# pcuTC.net
KiCad netlist of a schematic drawn in Altium Designer
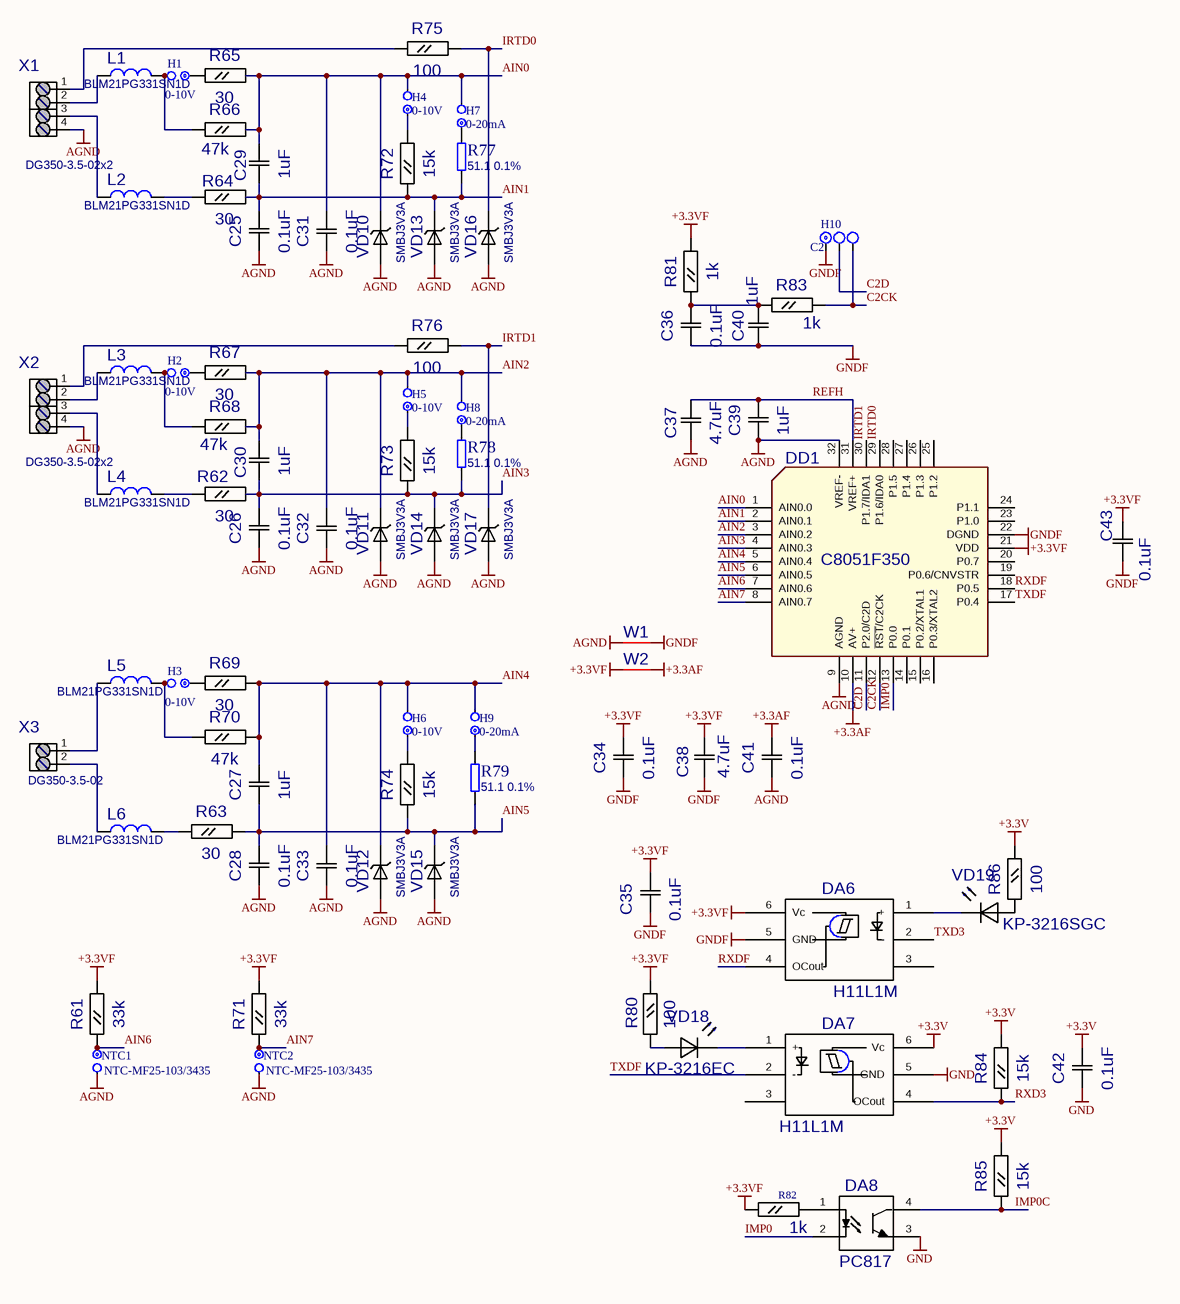
[diagram p0: pcuTC.SchDoc]

(export (version "E")
  (design (tool "Eeschema 10.0.6"))
  (components
    (comp (ref "C25")
      (value "0.1uF")
      (footprint "C0805")
      (description "C0805")
      (libsource (lib "FurmansLib") (part "C0805"))
    )
    (comp (ref "C26")
      (value "0.1uF")
      (footprint "C0805")
      (description "C0805")
      (libsource (lib "FurmansLib") (part "C0805"))
    )
    (comp (ref "C27")
      (value "1uF")
      (footprint "C0805")
      (description "C0805")
      (libsource (lib "FurmansLib") (part "C0805"))
    )
    (comp (ref "C28")
      (value "0.1uF")
      (footprint "C0805")
      (description "C0805")
      (libsource (lib "FurmansLib") (part "C0805"))
    )
    (comp (ref "C29")
      (value "1uF")
      (footprint "C0805")
      (description "C0805")
      (libsource (lib "FurmansLib") (part "C0805"))
    )
    (comp (ref "C30")
      (value "1uF")
      (footprint "C0805")
      (description "C0805")
      (libsource (lib "FurmansLib") (part "C0805"))
    )
    (comp (ref "C31")
      (value "0.1uF")
      (footprint "C0805")
      (description "C0805")
      (libsource (lib "FurmansLib") (part "C0805"))
    )
    (comp (ref "C32")
      (value "0.1uF")
      (footprint "C0805")
      (description "C0805")
      (libsource (lib "FurmansLib") (part "C0805"))
    )
    (comp (ref "C33")
      (value "0.1uF")
      (footprint "C0805")
      (description "C0805")
      (libsource (lib "FurmansLib") (part "C0805"))
    )
    (comp (ref "C34")
      (value "0.1uF")
      (footprint "C0805")
      (description "C0805")
      (libsource (lib "FurmansLib") (part "C0805"))
    )
    (comp (ref "C35")
      (value "0.1uF")
      (footprint "C0805")
      (description "C0805")
      (libsource (lib "FurmansLib") (part "C0805"))
    )
    (comp (ref "C36")
      (value "0.1uF")
      (footprint "C0805")
      (description "C0805")
      (libsource (lib "FurmansLib") (part "C0805"))
    )
    (comp (ref "C37")
      (value "4.7uF")
      (footprint "C0805")
      (description "C0805")
      (libsource (lib "FurmansLib") (part "C0805"))
    )
    (comp (ref "C38")
      (value "4.7uF")
      (footprint "C0805")
      (description "C0805")
      (libsource (lib "FurmansLib") (part "C0805"))
    )
    (comp (ref "C39")
      (value "1uF")
      (footprint "C0805")
      (description "C0805")
      (libsource (lib "FurmansLib") (part "C0805"))
    )
    (comp (ref "C40")
      (value "1uF")
      (footprint "C0805")
      (description "C0805")
      (libsource (lib "FurmansLib") (part "C0805"))
    )
    (comp (ref "C41")
      (value "0.1uF")
      (footprint "C0805")
      (description "C0805")
      (libsource (lib "FurmansLib") (part "C0805"))
    )
    (comp (ref "C42")
      (value "0.1uF")
      (footprint "C0805")
      (description "C0805")
      (libsource (lib "FurmansLib") (part "C0805"))
    )
    (comp (ref "C43")
      (value "0.1uF")
      (footprint "C0805")
      (description "C0805")
      (libsource (lib "FurmansLib") (part "C0805"))
    )
    (comp (ref "DA6") (value "H11L1M") (footprint "DIP6_SURFACE") (libsource (lib "") (part "H11L1M_1")))
    (comp (ref "DA7") (value "H11L1M") (footprint "DIP6_SURFACE") (libsource (lib "*") (part "H11L1M")))
    (comp (ref "DA8")
      (value "PC817")
      (footprint "DIL4SMD")
      (description "optocuple")
      (libsource (lib "FurmansLib") (part "PC817"))
    )
    (comp (ref "DD1")
      (value "C8051F350")
      (footprint "LQFP-32_N")
      (libsource (lib "FurmansLib") (part "C8051F350"))
    )
    (comp (ref "H1")
      (value "~")
      (footprint "J1x2")
      (fields (field (name "ALTIUM_UNNAMED_2") "0-10V"))
      (libsource (lib "FurmansLib") (part "H-1x2"))
    )
    (comp (ref "H2")
      (value "~")
      (footprint "J1x2")
      (fields (field (name "ALTIUM_UNNAMED_2") "0-10V"))
      (libsource (lib "FurmansLib") (part "H-1x2"))
    )
    (comp (ref "H3")
      (value "~")
      (footprint "J1x2")
      (fields (field (name "ALTIUM_UNNAMED_2") "0-10V"))
      (libsource (lib "FurmansLib") (part "H-1x2"))
    )
    (comp (ref "H4")
      (value "~")
      (footprint "J1x2")
      (fields (field (name "ALTIUM_UNNAMED_2") "0-10V"))
      (libsource (lib "FurmansLib") (part "H-1x2"))
    )
    (comp (ref "H5")
      (value "~")
      (footprint "J1x2")
      (fields (field (name "ALTIUM_UNNAMED_2") "0-10V"))
      (libsource (lib "FurmansLib") (part "H-1x2"))
    )
    (comp (ref "H6")
      (value "~")
      (footprint "J1x2")
      (fields (field (name "ALTIUM_UNNAMED_2") "0-10V"))
      (libsource (lib "FurmansLib") (part "H-1x2"))
    )
    (comp (ref "H7")
      (value "~")
      (footprint "J1x2")
      (fields (field (name "ALTIUM_UNNAMED_2") "0-20mA"))
      (libsource (lib "FurmansLib") (part "H-1x2"))
    )
    (comp (ref "H8")
      (value "~")
      (footprint "J1x2")
      (fields (field (name "ALTIUM_UNNAMED_2") "0-20mA"))
      (libsource (lib "FurmansLib") (part "H-1x2"))
    )
    (comp (ref "H9")
      (value "~")
      (footprint "J1x2")
      (fields (field (name "ALTIUM_UNNAMED_2") "0-20mA"))
      (libsource (lib "FurmansLib") (part "H-1x2"))
    )
    (comp (ref "H10") (value "C2") (footprint "J1x3") (libsource (lib "FurmansLib") (part "H-1x3")))
    (comp (ref "L1")
      (value "BLM21PG331SN1D")
      (footprint "R0805")
      (description "Ferrite beads")
      (libsource (lib "FurmansLib") (part "BLM21PG331SN1D"))
    )
    (comp (ref "L2")
      (value "BLM21PG331SN1D")
      (footprint "R0805")
      (description "Ferrite beads")
      (libsource (lib "FurmansLib") (part "BLM21PG331SN1D"))
    )
    (comp (ref "L3")
      (value "BLM21PG331SN1D")
      (footprint "R0805")
      (description "Ferrite beads")
      (libsource (lib "FurmansLib") (part "BLM21PG331SN1D"))
    )
    (comp (ref "L4")
      (value "BLM21PG331SN1D")
      (footprint "R0805")
      (description "Ferrite beads")
      (libsource (lib "FurmansLib") (part "BLM21PG331SN1D"))
    )
    (comp (ref "L5")
      (value "BLM21PG331SN1D")
      (footprint "R0805")
      (description "Ferrite beads")
      (libsource (lib "FurmansLib") (part "BLM21PG331SN1D"))
    )
    (comp (ref "L6")
      (value "BLM21PG331SN1D")
      (footprint "R0805")
      (description "Ferrite beads")
      (libsource (lib "FurmansLib") (part "BLM21PG331SN1D"))
    )
    (comp (ref "NTC1")
      (value "~")
      (footprint "J1x2")
      (fields (field (name "ALTIUM_UNNAMED_1") "NTC-MF25-103/3435"))
      (libsource (lib "FurmansLib") (part "H-1x2"))
    )
    (comp (ref "NTC2")
      (value "~")
      (footprint "J1x2")
      (fields (field (name "ALTIUM_UNNAMED_1") "NTC-MF25-103/3435"))
      (libsource (lib "FurmansLib") (part "H-1x2"))
    )
    (comp (ref "R61")
      (value "33k")
      (footprint "R0805")
      (description "R0805")
      (libsource (lib "FurmansLib") (part "R0805"))
    )
    (comp (ref "R62")
      (value "30")
      (footprint "R0805")
      (description "R0805")
      (libsource (lib "FurmansLib") (part "R0805"))
    )
    (comp (ref "R63")
      (value "30")
      (footprint "R0805")
      (description "R0805")
      (libsource (lib "FurmansLib") (part "R0805"))
    )
    (comp (ref "R64")
      (value "30")
      (footprint "R0805")
      (description "R0805")
      (libsource (lib "FurmansLib") (part "R0805"))
    )
    (comp (ref "R65")
      (value "30")
      (footprint "R0805")
      (description "R0805")
      (libsource (lib "FurmansLib") (part "R0805"))
    )
    (comp (ref "R66")
      (value "47k")
      (footprint "R0805")
      (description "R0805")
      (libsource (lib "FurmansLib") (part "R0805"))
    )
    (comp (ref "R67")
      (value "30")
      (footprint "R0805")
      (description "R0805")
      (libsource (lib "FurmansLib") (part "R0805"))
    )
    (comp (ref "R68")
      (value "47k")
      (footprint "R0805")
      (description "R0805")
      (libsource (lib "FurmansLib") (part "R0805"))
    )
    (comp (ref "R69")
      (value "30")
      (footprint "R0805")
      (description "R0805")
      (libsource (lib "FurmansLib") (part "R0805"))
    )
    (comp (ref "R70")
      (value "47k")
      (footprint "R0805")
      (description "R0805")
      (libsource (lib "FurmansLib") (part "R0805"))
    )
    (comp (ref "R71")
      (value "33k")
      (footprint "R0805")
      (description "R0805")
      (libsource (lib "FurmansLib") (part "R0805"))
    )
    (comp (ref "R72")
      (value "15k")
      (footprint "R0805")
      (description "R0805")
      (libsource (lib "FurmansLib") (part "R0805"))
    )
    (comp (ref "R73")
      (value "15k")
      (footprint "R0805")
      (description "R0805")
      (libsource (lib "FurmansLib") (part "R0805"))
    )
    (comp (ref "R74")
      (value "15k")
      (footprint "R0805")
      (description "R0805")
      (libsource (lib "FurmansLib") (part "R0805"))
    )
    (comp (ref "R75")
      (value "100")
      (footprint "R0805")
      (description "R0805")
      (libsource (lib "FurmansLib") (part "R0805"))
    )
    (comp (ref "R76")
      (value "100")
      (footprint "R0805")
      (description "R0805")
      (libsource (lib "FurmansLib") (part "R0805"))
    )
    (comp (ref "R77")
      (value "51.1 0.1%")
      (footprint "R0.25-300")
      (description "0.25W 5% 250V")
      (libsource (lib "Rez-Axial Pot") (part "R-0.25W"))
    )
    (comp (ref "R78")
      (value "51.1 0.1%")
      (footprint "R0.25-300")
      (description "0.25W 5% 250V")
      (libsource (lib "Rez-Axial Pot") (part "R-0.25W"))
    )
    (comp (ref "R79")
      (value "51.1 0.1%")
      (footprint "R0.25-300")
      (description "0.25W 5% 250V")
      (libsource (lib "Rez-Axial Pot") (part "R-0.25W"))
    )
    (comp (ref "R80")
      (value "100")
      (footprint "R0805")
      (description "R0805")
      (libsource (lib "*") (part "R0805"))
    )
    (comp (ref "R81")
      (value "1k")
      (footprint "R0805")
      (description "R0805")
      (libsource (lib "FurmansLib") (part "R0805"))
    )
    (comp (ref "R82")
      (value "1k")
      (footprint "R0805")
      (description "R0805")
      (libsource (lib "FurmansLib") (part "R0805"))
    )
    (comp (ref "R83")
      (value "1k")
      (footprint "R0805")
      (description "R0805")
      (libsource (lib "FurmansLib") (part "R0805"))
    )
    (comp (ref "R84")
      (value "15k")
      (footprint "R0805")
      (description "R0805")
      (libsource (lib "FurmansLib") (part "R0805"))
    )
    (comp (ref "R85")
      (value "15k")
      (footprint "R0805")
      (description "R0805")
      (libsource (lib "FurmansLib") (part "R0805"))
    )
    (comp (ref "R86")
      (value "100")
      (footprint "R0805")
      (description "R0805")
      (libsource (lib "*") (part "R0805"))
    )
    (comp (ref "VD10")
      (value "SMBJ3V3A")
      (footprint "DO-214AA(SMB)")
      (description "10BQ100")
      (libsource (lib "FurmansLib") (part "10BQ100"))
    )
    (comp (ref "VD11")
      (value "SMBJ3V3A")
      (footprint "DO-214AA(SMB)")
      (description "10BQ100")
      (libsource (lib "FurmansLib") (part "10BQ100"))
    )
    (comp (ref "VD12")
      (value "SMBJ3V3A")
      (footprint "DO-214AA(SMB)")
      (description "10BQ100")
      (libsource (lib "FurmansLib") (part "10BQ100"))
    )
    (comp (ref "VD13")
      (value "SMBJ3V3A")
      (footprint "DO-214AA(SMB)")
      (description "10BQ100")
      (libsource (lib "FurmansLib") (part "10BQ100"))
    )
    (comp (ref "VD14")
      (value "SMBJ3V3A")
      (footprint "DO-214AA(SMB)")
      (description "10BQ100")
      (libsource (lib "FurmansLib") (part "10BQ100"))
    )
    (comp (ref "VD15")
      (value "SMBJ3V3A")
      (footprint "DO-214AA(SMB)")
      (description "10BQ100")
      (libsource (lib "FurmansLib") (part "10BQ100"))
    )
    (comp (ref "VD16")
      (value "SMBJ3V3A")
      (footprint "DO-214AA(SMB)")
      (description "10BQ100")
      (libsource (lib "FurmansLib") (part "10BQ100"))
    )
    (comp (ref "VD17")
      (value "SMBJ3V3A")
      (footprint "DO-214AA(SMB)")
      (description "10BQ100")
      (libsource (lib "FurmansLib") (part "10BQ100"))
    )
    (comp (ref "VD18") (value "KP-3216EC") (footprint "KP-3216") (libsource (lib "*") (part "KP-3216EC")))
    (comp (ref "VD19") (value "KP-3216SGC") (footprint "KP-3216") (libsource (lib "*") (part "KP-3216SGC")))
    (comp (ref "W1")
      (value "Net connector")
      (footprint "FurmansLib:Net connector0.5mm")
      (description "NET CONNECTOR")
      (libsource (lib "Furmans") (part "Net connector"))
    )
    (comp (ref "W2")
      (value "Net connector")
      (footprint "FurmansLib:Net connector0.5mm")
      (description "NET CONNECTOR")
      (libsource (lib "Furmans") (part "Net connector"))
    )
    (comp (ref "X1")
      (value "DG350-3.5-02x2")
      (footprint "DG350-3.5-04 SLIM - duplicate")
      (libsource (lib "FurmansLib") (part "DG350-3.5-04"))
    )
    (comp (ref "X2")
      (value "DG350-3.5-02x2")
      (footprint "DG350-3.5-04 SLIM - duplicate")
      (libsource (lib "FurmansLib") (part "DG350-3.5-04"))
    )
    (comp (ref "X3")
      (value "DG350-3.5-02")
      (footprint "DG350-3.5-02 SLIM")
      (libsource (lib "FurmansLib") (part "DG350-3.5-02"))
    )
  )
  (nets
    (net (code "1") (name "+3.3AF") (class "Default")
      (node (ref "C41") (pin "2") (pintype "passive"))
      (node (ref "DD1") (pin "10") (pinfunction "AV+_10") (pintype "passive"))
      (node (ref "W2") (pin "1") (pintype "passive"))
    )
    (net (code "2") (name "+3.3V") (class "Default")
      (node (ref "C42") (pin "2") (pintype "passive"))
      (node (ref "DA7") (pin "6") (pinfunction "Vc_6") (pintype "passive"))
      (node (ref "R84") (pin "1") (pintype "passive"))
      (node (ref "R85") (pin "1") (pintype "passive"))
      (node (ref "R86") (pin "2") (pintype "passive"))
    )
    (net (code "3") (name "+3.3VF") (class "Default")
      (node (ref "C34") (pin "2") (pintype "passive"))
      (node (ref "C35") (pin "1") (pintype "passive"))
      (node (ref "C38") (pin "2") (pintype "passive"))
      (node (ref "C43") (pin "2") (pintype "passive"))
      (node (ref "DA6") (pin "6") (pinfunction "Vc_6") (pintype "passive"))
      (node (ref "DD1") (pin "21") (pinfunction "VDD_21") (pintype "passive"))
      (node (ref "R61") (pin "1") (pintype "passive"))
      (node (ref "R71") (pin "1") (pintype "passive"))
      (node (ref "R80") (pin "2") (pintype "passive"))
      (node (ref "R81") (pin "1") (pintype "passive"))
      (node (ref "R82") (pin "2") (pintype "passive"))
      (node (ref "W2") (pin "2") (pintype "passive"))
    )
    (net (code "4") (name "/AIN0") (class "Default")
      (node (ref "C29") (pin "2") (pintype "passive"))
      (node (ref "C31") (pin "1") (pintype "passive"))
      (node (ref "DD1") (pin "1") (pinfunction "AIN0.0_1") (pintype "passive"))
      (node (ref "H4") (pin "2") (pinfunction "2_2") (pintype "passive"))
      (node (ref "H7") (pin "2") (pinfunction "2_2") (pintype "passive"))
      (node (ref "R65") (pin "1") (pintype "passive"))
      (node (ref "R66") (pin "1") (pintype "passive"))
      (node (ref "VD10") (pin "1") (pintype "passive"))
    )
    (net (code "5") (name "/AIN1") (class "Default")
      (node (ref "C25") (pin "2") (pintype "passive"))
      (node (ref "C29") (pin "1") (pintype "passive"))
      (node (ref "DD1") (pin "2") (pinfunction "AIN0.1_2") (pintype "passive"))
      (node (ref "R64") (pin "1") (pintype "passive"))
      (node (ref "R72") (pin "2") (pintype "passive"))
      (node (ref "R77") (pin "1") (pinfunction "1_1") (pintype "passive"))
      (node (ref "VD13") (pin "1") (pintype "passive"))
    )
    (net (code "6") (name "/AIN2") (class "Default")
      (node (ref "C30") (pin "2") (pintype "passive"))
      (node (ref "C32") (pin "1") (pintype "passive"))
      (node (ref "DD1") (pin "3") (pinfunction "AIN0.2_3") (pintype "passive"))
      (node (ref "H5") (pin "2") (pinfunction "2_2") (pintype "passive"))
      (node (ref "H8") (pin "2") (pinfunction "2_2") (pintype "passive"))
      (node (ref "R67") (pin "1") (pintype "passive"))
      (node (ref "R68") (pin "1") (pintype "passive"))
      (node (ref "VD11") (pin "1") (pintype "passive"))
    )
    (net (code "7") (name "/AIN3") (class "Default")
      (node (ref "C26") (pin "2") (pintype "passive"))
      (node (ref "C30") (pin "1") (pintype "passive"))
      (node (ref "DD1") (pin "4") (pinfunction "AIN0.3_4") (pintype "passive"))
      (node (ref "R62") (pin "1") (pintype "passive"))
      (node (ref "R73") (pin "2") (pintype "passive"))
      (node (ref "R78") (pin "1") (pinfunction "1_1") (pintype "passive"))
      (node (ref "VD14") (pin "1") (pintype "passive"))
    )
    (net (code "8") (name "/AIN4") (class "Default")
      (node (ref "C27") (pin "2") (pintype "passive"))
      (node (ref "C33") (pin "1") (pintype "passive"))
      (node (ref "DD1") (pin "5") (pinfunction "AIN0.4_5") (pintype "passive"))
      (node (ref "H6") (pin "2") (pinfunction "2_2") (pintype "passive"))
      (node (ref "H9") (pin "2") (pinfunction "2_2") (pintype "passive"))
      (node (ref "R69") (pin "1") (pintype "passive"))
      (node (ref "R70") (pin "1") (pintype "passive"))
      (node (ref "VD12") (pin "1") (pintype "passive"))
    )
    (net (code "9") (name "/AIN5") (class "Default")
      (node (ref "C27") (pin "1") (pintype "passive"))
      (node (ref "C28") (pin "2") (pintype "passive"))
      (node (ref "DD1") (pin "6") (pinfunction "AIN0.5_6") (pintype "passive"))
      (node (ref "R63") (pin "1") (pintype "passive"))
      (node (ref "R74") (pin "2") (pintype "passive"))
      (node (ref "R79") (pin "1") (pinfunction "1_1") (pintype "passive"))
      (node (ref "VD15") (pin "1") (pintype "passive"))
    )
    (net (code "10") (name "/AIN6") (class "Default")
      (node (ref "DD1") (pin "7") (pinfunction "AIN0.6_7") (pintype "passive"))
      (node (ref "NTC1") (pin "1") (pinfunction "1_1") (pintype "passive"))
      (node (ref "R61") (pin "2") (pintype "passive"))
    )
    (net (code "11") (name "/AIN7") (class "Default")
      (node (ref "DD1") (pin "8") (pinfunction "AIN0.7_8") (pintype "passive"))
      (node (ref "NTC2") (pin "1") (pinfunction "1_1") (pintype "passive"))
      (node (ref "R71") (pin "2") (pintype "passive"))
    )
    (net (code "12") (name "/C2CK") (class "Default")
      (node (ref "DD1") (pin "12") (pinfunction "~{RST}/C2CK_12") (pintype "passive"))
      (node (ref "H10") (pin "3") (pinfunction "3_3") (pintype "passive"))
      (node (ref "R83") (pin "1") (pintype "passive"))
    )
    (net (code "13") (name "/C2D") (class "Default")
      (node (ref "DD1") (pin "11") (pinfunction "P2.0/C2D_11") (pintype "passive"))
      (node (ref "H10") (pin "2") (pinfunction "2_2") (pintype "passive"))
    )
    (net (code "14") (name "/IMP0") (class "Default")
      (node (ref "DA8") (pin "2") (pinfunction "-_2") (pintype "passive"))
      (node (ref "DD1") (pin "13") (pinfunction "P0.0_13") (pintype "passive"))
    )
    (net (code "15") (name "/IMP0C") (class "Default")
      (node (ref "DA8") (pin "4") (pinfunction "C_4") (pintype "passive"))
      (node (ref "R85") (pin "2") (pintype "passive"))
    )
    (net (code "16") (name "/IRTD0") (class "Default")
      (node (ref "DD1") (pin "29") (pinfunction "P1.6/IDA0_29") (pintype "passive"))
      (node (ref "R75") (pin "1") (pintype "passive"))
      (node (ref "VD16") (pin "1") (pintype "passive"))
    )
    (net (code "17") (name "/IRTD1") (class "Default")
      (node (ref "DD1") (pin "30") (pinfunction "P1.7/IDA1_30") (pintype "passive"))
      (node (ref "R76") (pin "1") (pintype "passive"))
      (node (ref "VD17") (pin "1") (pintype "passive"))
    )
    (net (code "18") (name "/REFH") (class "Default")
      (node (ref "C37") (pin "1") (pintype "passive"))
      (node (ref "C39") (pin "2") (pintype "passive"))
      (node (ref "DD1") (pin "31") (pinfunction "VREF+_31") (pintype "passive"))
    )
    (net (code "19") (name "/RXD3") (class "Default")
      (node (ref "DA7") (pin "4") (pinfunction "OCout_4") (pintype "passive"))
      (node (ref "R84") (pin "2") (pintype "passive"))
    )
    (net (code "20") (name "/RXDF") (class "Default")
      (node (ref "DA6") (pin "4") (pinfunction "OCout_4") (pintype "passive"))
      (node (ref "DD1") (pin "18") (pinfunction "P0.5_18") (pintype "passive"))
    )
    (net (code "21") (name "/TXD3") (class "Default")
      (node (ref "DA6") (pin "2") (pinfunction "-_2") (pintype "passive"))
    )
    (net (code "22") (name "/TXDF") (class "Default")
      (node (ref "DA7") (pin "2") (pinfunction "-_2") (pintype "passive"))
      (node (ref "DD1") (pin "17") (pinfunction "P0.4_17") (pintype "passive"))
    )
    (net (code "23") (name "AGND") (class "Default")
      (node (ref "C25") (pin "1") (pintype "passive"))
      (node (ref "C26") (pin "1") (pintype "passive"))
      (node (ref "C28") (pin "1") (pintype "passive"))
      (node (ref "C31") (pin "2") (pintype "passive"))
      (node (ref "C32") (pin "2") (pintype "passive"))
      (node (ref "C33") (pin "2") (pintype "passive"))
      (node (ref "C37") (pin "2") (pintype "passive"))
      (node (ref "C39") (pin "1") (pintype "passive"))
      (node (ref "C41") (pin "1") (pintype "passive"))
      (node (ref "DD1") (pin "32") (pinfunction "VREF-_32") (pintype "passive"))
      (node (ref "DD1") (pin "9") (pinfunction "AGND_9") (pintype "passive"))
      (node (ref "NTC1") (pin "2") (pinfunction "2_2") (pintype "passive"))
      (node (ref "NTC2") (pin "2") (pinfunction "2_2") (pintype "passive"))
      (node (ref "VD10") (pin "2") (pintype "passive"))
      (node (ref "VD11") (pin "2") (pintype "passive"))
      (node (ref "VD12") (pin "2") (pintype "passive"))
      (node (ref "VD13") (pin "2") (pintype "passive"))
      (node (ref "VD14") (pin "2") (pintype "passive"))
      (node (ref "VD15") (pin "2") (pintype "passive"))
      (node (ref "VD16") (pin "2") (pintype "passive"))
      (node (ref "VD17") (pin "2") (pintype "passive"))
      (node (ref "W1") (pin "2") (pintype "passive"))
      (node (ref "X1") (pin "4") (pintype "passive"))
      (node (ref "X2") (pin "4") (pintype "passive"))
    )
    (net (code "24") (name "GND") (class "Default")
      (node (ref "C42") (pin "1") (pintype "passive"))
      (node (ref "DA7") (pin "5") (pinfunction "GND_5") (pintype "passive"))
      (node (ref "DA8") (pin "3") (pinfunction "E_3") (pintype "passive"))
    )
    (net (code "25") (name "GNDF") (class "Default")
      (node (ref "C34") (pin "1") (pintype "passive"))
      (node (ref "C35") (pin "2") (pintype "passive"))
      (node (ref "C36") (pin "1") (pintype "passive"))
      (node (ref "C38") (pin "1") (pintype "passive"))
      (node (ref "C40") (pin "1") (pintype "passive"))
      (node (ref "C43") (pin "1") (pintype "passive"))
      (node (ref "DA6") (pin "5") (pinfunction "GND_5") (pintype "passive"))
      (node (ref "DD1") (pin "22") (pinfunction "DGND_22") (pintype "passive"))
      (node (ref "H10") (pin "1") (pinfunction "1_1") (pintype "passive"))
      (node (ref "W1") (pin "1") (pintype "passive"))
    )
    (net (code "26") (name "Net-(C36-Pad2)") (class "Default")
      (node (ref "C36") (pin "2") (pintype "passive"))
      (node (ref "C40") (pin "2") (pintype "passive"))
      (node (ref "R81") (pin "2") (pintype "passive"))
      (node (ref "R83") (pin "2") (pintype "passive"))
    )
    (net (code "27") (name "Net-(DA6-+)") (class "Default")
      (node (ref "DA6") (pin "1") (pinfunction "+_1") (pintype "passive"))
      (node (ref "VD19") (pin "2") (pintype "passive"))
    )
    (net (code "28") (name "Net-(DA7-+)") (class "Default")
      (node (ref "DA7") (pin "1") (pinfunction "+_1") (pintype "passive"))
      (node (ref "VD18") (pin "2") (pintype "passive"))
    )
    (net (code "29") (name "Net-(DA8-+)") (class "Default")
      (node (ref "DA8") (pin "1") (pinfunction "+_1") (pintype "passive"))
      (node (ref "R82") (pin "1") (pintype "passive"))
    )
    (net (code "30") (name "Net-(H1-Pad1)") (class "Default")
      (node (ref "H1") (pin "1") (pinfunction "1_1") (pintype "passive"))
      (node (ref "R65") (pin "2") (pintype "passive"))
    )
    (net (code "31") (name "Net-(H1-Pad2)") (class "Default")
      (node (ref "H1") (pin "2") (pinfunction "2_2") (pintype "passive"))
      (node (ref "L1") (pin "2") (pintype "passive"))
      (node (ref "R66") (pin "2") (pintype "passive"))
    )
    (net (code "32") (name "Net-(H2-Pad1)") (class "Default")
      (node (ref "H2") (pin "1") (pinfunction "1_1") (pintype "passive"))
      (node (ref "R67") (pin "2") (pintype "passive"))
    )
    (net (code "33") (name "Net-(H2-Pad2)") (class "Default")
      (node (ref "H2") (pin "2") (pinfunction "2_2") (pintype "passive"))
      (node (ref "L3") (pin "2") (pintype "passive"))
      (node (ref "R68") (pin "2") (pintype "passive"))
    )
    (net (code "34") (name "Net-(H3-Pad1)") (class "Default")
      (node (ref "H3") (pin "1") (pinfunction "1_1") (pintype "passive"))
      (node (ref "R69") (pin "2") (pintype "passive"))
    )
    (net (code "35") (name "Net-(H3-Pad2)") (class "Default")
      (node (ref "H3") (pin "2") (pinfunction "2_2") (pintype "passive"))
      (node (ref "L5") (pin "2") (pintype "passive"))
      (node (ref "R70") (pin "2") (pintype "passive"))
    )
    (net (code "36") (name "Net-(H4-Pad1)") (class "Default")
      (node (ref "H4") (pin "1") (pinfunction "1_1") (pintype "passive"))
      (node (ref "R72") (pin "1") (pintype "passive"))
    )
    (net (code "37") (name "Net-(H5-Pad1)") (class "Default")
      (node (ref "H5") (pin "1") (pinfunction "1_1") (pintype "passive"))
      (node (ref "R73") (pin "1") (pintype "passive"))
    )
    (net (code "38") (name "Net-(H6-Pad1)") (class "Default")
      (node (ref "H6") (pin "1") (pinfunction "1_1") (pintype "passive"))
      (node (ref "R74") (pin "1") (pintype "passive"))
    )
    (net (code "39") (name "Net-(H7-Pad1)") (class "Default")
      (node (ref "H7") (pin "1") (pinfunction "1_1") (pintype "passive"))
      (node (ref "R77") (pin "2") (pinfunction "2_2") (pintype "passive"))
    )
    (net (code "40") (name "Net-(H8-Pad1)") (class "Default")
      (node (ref "H8") (pin "1") (pinfunction "1_1") (pintype "passive"))
      (node (ref "R78") (pin "2") (pinfunction "2_2") (pintype "passive"))
    )
    (net (code "41") (name "Net-(H9-Pad1)") (class "Default")
      (node (ref "H9") (pin "1") (pinfunction "1_1") (pintype "passive"))
      (node (ref "R79") (pin "2") (pinfunction "2_2") (pintype "passive"))
    )
    (net (code "42") (name "Net-(L1-Pad1)") (class "Default")
      (node (ref "L1") (pin "1") (pintype "passive"))
      (node (ref "X1") (pin "2") (pintype "passive"))
    )
    (net (code "43") (name "Net-(L2-Pad1)") (class "Default")
      (node (ref "L2") (pin "1") (pintype "passive"))
      (node (ref "X1") (pin "3") (pintype "passive"))
    )
    (net (code "44") (name "Net-(L2-Pad2)") (class "Default")
      (node (ref "L2") (pin "2") (pintype "passive"))
      (node (ref "R64") (pin "2") (pintype "passive"))
    )
    (net (code "45") (name "Net-(L3-Pad1)") (class "Default")
      (node (ref "L3") (pin "1") (pintype "passive"))
      (node (ref "X2") (pin "2") (pintype "passive"))
    )
    (net (code "46") (name "Net-(L4-Pad1)") (class "Default")
      (node (ref "L4") (pin "1") (pintype "passive"))
      (node (ref "X2") (pin "3") (pintype "passive"))
    )
    (net (code "47") (name "Net-(L4-Pad2)") (class "Default")
      (node (ref "L4") (pin "2") (pintype "passive"))
      (node (ref "R62") (pin "2") (pintype "passive"))
    )
    (net (code "48") (name "Net-(L5-Pad1)") (class "Default")
      (node (ref "L5") (pin "1") (pintype "passive"))
      (node (ref "X3") (pin "1") (pintype "passive"))
    )
    (net (code "49") (name "Net-(L6-Pad1)") (class "Default")
      (node (ref "L6") (pin "1") (pintype "passive"))
      (node (ref "X3") (pin "2") (pintype "passive"))
    )
    (net (code "50") (name "Net-(L6-Pad2)") (class "Default")
      (node (ref "L6") (pin "2") (pintype "passive"))
      (node (ref "R63") (pin "2") (pintype "passive"))
    )
    (net (code "51") (name "Net-(R75-Pad2)") (class "Default")
      (node (ref "R75") (pin "2") (pintype "passive"))
      (node (ref "X1") (pin "1") (pintype "passive"))
    )
    (net (code "52") (name "Net-(R76-Pad2)") (class "Default")
      (node (ref "R76") (pin "2") (pintype "passive"))
      (node (ref "X2") (pin "1") (pintype "passive"))
    )
    (net (code "53") (name "Net-(R80-Pad1)") (class "Default")
      (node (ref "R80") (pin "1") (pintype "passive"))
      (node (ref "VD18") (pin "1") (pintype "passive"))
    )
    (net (code "54") (name "Net-(R86-Pad1)") (class "Default")
      (node (ref "R86") (pin "1") (pintype "passive"))
      (node (ref "VD19") (pin "1") (pintype "passive"))
    )
    (net (code "55") (name "unconnected-(DA6-Pad3)") (class "Default")
      (node (ref "DA6") (pin "3") (pintype "passive"))
    )
    (net (code "56") (name "unconnected-(DA7-Pad3)") (class "Default")
      (node (ref "DA7") (pin "3") (pintype "passive"))
    )
    (net (code "57") (name "unconnected-(DD1-P0.1-Pad14)") (class "Default")
      (node (ref "DD1") (pin "14") (pinfunction "P0.1_14") (pintype "passive"))
    )
    (net (code "58") (name "unconnected-(DD1-P0.2{slash}XTAL1-Pad15)") (class "Default")
      (node (ref "DD1") (pin "15") (pinfunction "P0.2/XTAL1_15") (pintype "passive"))
    )
    (net (code "59") (name "unconnected-(DD1-P0.3{slash}XTAL2-Pad16)") (class "Default")
      (node (ref "DD1") (pin "16") (pinfunction "P0.3/XTAL2_16") (pintype "passive"))
    )
    (net (code "60") (name "unconnected-(DD1-P0.6{slash}CNVSTR-Pad19)") (class "Default")
      (node (ref "DD1") (pin "19") (pinfunction "P0.6/CNVSTR_19") (pintype "passive"))
    )
    (net (code "61") (name "unconnected-(DD1-P0.7-Pad20)") (class "Default")
      (node (ref "DD1") (pin "20") (pinfunction "P0.7_20") (pintype "passive"))
    )
    (net (code "62") (name "unconnected-(DD1-P1.0-Pad23)") (class "Default")
      (node (ref "DD1") (pin "23") (pinfunction "P1.0_23") (pintype "passive"))
    )
    (net (code "63") (name "unconnected-(DD1-P1.1-Pad24)") (class "Default")
      (node (ref "DD1") (pin "24") (pinfunction "P1.1_24") (pintype "passive"))
    )
    (net (code "64") (name "unconnected-(DD1-P1.2-Pad25)") (class "Default")
      (node (ref "DD1") (pin "25") (pinfunction "P1.2_25") (pintype "passive"))
    )
    (net (code "65") (name "unconnected-(DD1-P1.3-Pad26)") (class "Default")
      (node (ref "DD1") (pin "26") (pinfunction "P1.3_26") (pintype "passive"))
    )
    (net (code "66") (name "unconnected-(DD1-P1.4-Pad27)") (class "Default")
      (node (ref "DD1") (pin "27") (pinfunction "P1.4_27") (pintype "passive"))
    )
    (net (code "67") (name "unconnected-(DD1-P1.5-Pad28)") (class "Default")
      (node (ref "DD1") (pin "28") (pinfunction "P1.5_28") (pintype "passive"))
    )
  )
)
